# Mabee_Soil_Moisture_Sensor_v1_0.net
KiCad netlist of a schematic drawn in EAGLE
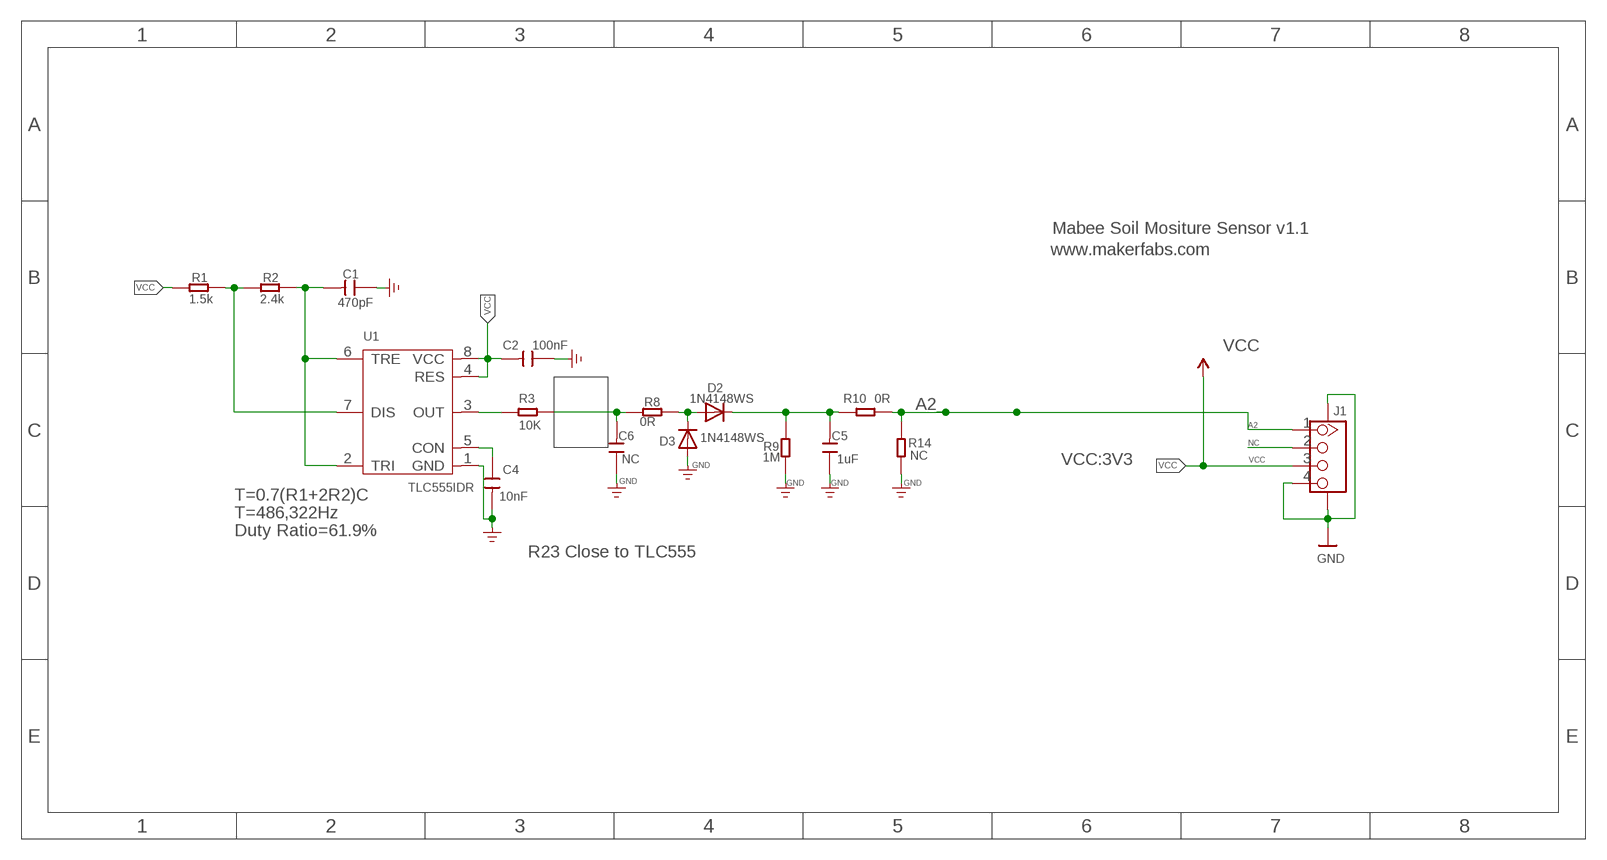
[diagram p0: schematic, sheet 1]

(export (version "E")
  (design (tool "Eeschema 10.0.6"))
  (components
    (comp (ref "C1")
      (value "470pF")
      (footprint "eagle-import:C0603")
      (libsource (lib "eagle-import") (part "CAP-0603"))
    )
    (comp (ref "C2")
      (value "100nF")
      (footprint "eagle-import:C0603")
      (libsource (lib "eagle-import") (part "CAP-0603"))
    )
    (comp (ref "C4")
      (value "10nF")
      (footprint "eagle-import:C0603")
      (libsource (lib "eagle-import") (part "CAP-0603"))
    )
    (comp (ref "C5")
      (value "1uF")
      (footprint "eagle-import:DISCRETE_C0603")
      (libsource (lib "eagle-import") (part "DISCRETE_C-0603"))
    )
    (comp (ref "C6")
      (value "NC")
      (footprint "eagle-import:DISCRETE_C0603")
      (libsource (lib "eagle-import") (part "DISCRETE_C-0603"))
    )
    (comp (ref "D2")
      (value "1N4148WS")
      (footprint "eagle-import:SOD-323F")
      (libsource (lib "eagle-import") (part "DIODESOD-323F"))
    )
    (comp (ref "D3")
      (value "1N4148WS")
      (footprint "eagle-import:SOD-323F")
      (libsource (lib "eagle-import") (part "DIODESOD-323F"))
    )
    (comp (ref "J1")
      (value "J1")
      (footprint "eagle-import:HW4-SMD-2.0-90D")
      (libsource (lib "eagle-import") (part "GROVE-CONNECTOR-SMD'90D'"))
    )
    (comp (ref "R1")
      (value "1.5k")
      (footprint "eagle-import:R0603")
      (libsource (lib "eagle-import") (part "RES-0603"))
    )
    (comp (ref "R2")
      (value "2.4k")
      (footprint "eagle-import:R0603")
      (libsource (lib "eagle-import") (part "RES-0603"))
    )
    (comp (ref "R3")
      (value "10K")
      (footprint "eagle-import:R0603")
      (libsource (lib "eagle-import") (part "RES-0603"))
    )
    (comp (ref "R8")
      (value "0R")
      (footprint "eagle-import:R0603")
      (libsource (lib "eagle-import") (part "R-0603"))
    )
    (comp (ref "R9")
      (value "1M")
      (footprint "eagle-import:R0603")
      (libsource (lib "eagle-import") (part "R-0603"))
    )
    (comp (ref "R10")
      (value "0R")
      (footprint "eagle-import:R0603")
      (libsource (lib "eagle-import") (part "R-0603"))
    )
    (comp (ref "R14")
      (value "NC")
      (footprint "eagle-import:R0603")
      (libsource (lib "eagle-import") (part "R-0603"))
    )
    (comp (ref "U1")
      (value "TLC555IDR")
      (footprint "eagle-import:SOIC8-1.27-5X4MM")
      (libsource (lib "eagle-import") (part "CLOCK/TIMING-NE555'DR'"))
    )
  )
  (nets
    (net (code "1") (name "/A2") (class "Default")
      (node (ref "J1") (pin "1") (pinfunction "1_1") (pintype "bidirectional"))
      (node (ref "R10") (pin "2") (pinfunction "2_2") (pintype "passive"))
      (node (ref "R14") (pin "1") (pinfunction "1_1") (pintype "passive"))
    )
    (net (code "2") (name "/NC") (class "Default")
      (node (ref "J1") (pin "2") (pinfunction "2_2") (pintype "bidirectional"))
    )
    (net (code "3") (name "GND") (class "Default")
      (node (ref "C1") (pin "1") (pinfunction "1_1") (pintype "passive"))
      (node (ref "C2") (pin "1") (pinfunction "1_1") (pintype "passive"))
      (node (ref "C4") (pin "2") (pinfunction "2_2") (pintype "passive"))
      (node (ref "C5") (pin "1") (pinfunction "1_1") (pintype "passive"))
      (node (ref "C6") (pin "1") (pinfunction "1_1") (pintype "passive"))
      (node (ref "D3") (pin "A") (pinfunction "A_A") (pintype "passive"))
      (node (ref "J1") (pin "4") (pinfunction "4_4") (pintype "bidirectional"))
      (node (ref "J1") (pin "SS1") (pinfunction "SS1_SS1") (pintype "bidirectional"))
      (node (ref "J1") (pin "SS2") (pinfunction "SS2_SS2") (pintype "bidirectional"))
      (node (ref "R14") (pin "2") (pinfunction "2_2") (pintype "passive"))
      (node (ref "R9") (pin "1") (pinfunction "1_1") (pintype "passive"))
      (node (ref "U1") (pin "1") (pinfunction "GND_1") (pintype "bidirectional"))
    )
    (net (code "4") (name "Net-(C5-Pad2)") (class "Default")
      (node (ref "C5") (pin "2") (pinfunction "2_2") (pintype "passive"))
      (node (ref "D2") (pin "C") (pinfunction "C_C") (pintype "passive"))
      (node (ref "R10") (pin "1") (pinfunction "1_1") (pintype "passive"))
      (node (ref "R9") (pin "2") (pinfunction "2_2") (pintype "passive"))
    )
    (net (code "5") (name "Net-(C6-Pad2)") (class "Default")
      (node (ref "C6") (pin "2") (pinfunction "2_2") (pintype "passive"))
      (node (ref "R3") (pin "2") (pinfunction "2_2") (pintype "passive"))
      (node (ref "R8") (pin "1") (pinfunction "1_1") (pintype "passive"))
    )
    (net (code "6") (name "Net-(D2-PadA)") (class "Default")
      (node (ref "D2") (pin "A") (pinfunction "A_A") (pintype "passive"))
      (node (ref "D3") (pin "C") (pinfunction "C_C") (pintype "passive"))
      (node (ref "R8") (pin "2") (pinfunction "2_2") (pintype "passive"))
    )
    (net (code "7") (name "Net-(U1-CON)") (class "Default")
      (node (ref "C4") (pin "1") (pinfunction "1_1") (pintype "passive"))
      (node (ref "U1") (pin "5") (pinfunction "CON_5") (pintype "bidirectional"))
    )
    (net (code "8") (name "Net-(U1-DIS)") (class "Default")
      (node (ref "R1") (pin "1") (pinfunction "1_1") (pintype "passive"))
      (node (ref "R2") (pin "2") (pinfunction "2_2") (pintype "passive"))
      (node (ref "U1") (pin "7") (pinfunction "DIS_7") (pintype "bidirectional"))
    )
    (net (code "9") (name "Net-(U1-OUT)") (class "Default")
      (node (ref "R3") (pin "1") (pinfunction "1_1") (pintype "passive"))
      (node (ref "U1") (pin "3") (pinfunction "OUT_3") (pintype "bidirectional"))
    )
    (net (code "10") (name "Net-(U1-TRE)") (class "Default")
      (node (ref "C1") (pin "2") (pinfunction "2_2") (pintype "passive"))
      (node (ref "R2") (pin "1") (pinfunction "1_1") (pintype "passive"))
      (node (ref "U1") (pin "2") (pinfunction "TRI_2") (pintype "bidirectional"))
      (node (ref "U1") (pin "6") (pinfunction "TRE_6") (pintype "bidirectional"))
    )
    (net (code "11") (name "VCC") (class "Default")
      (node (ref "C2") (pin "2") (pinfunction "2_2") (pintype "passive"))
      (node (ref "J1") (pin "3") (pinfunction "3_3") (pintype "bidirectional"))
      (node (ref "R1") (pin "2") (pinfunction "2_2") (pintype "passive"))
      (node (ref "U1") (pin "4") (pinfunction "RES_4") (pintype "bidirectional"))
      (node (ref "U1") (pin "8") (pinfunction "VCC_8") (pintype "bidirectional"))
    )
  )
)
